# power.net
KiCad netlist of a schematic drawn in Altium Designer
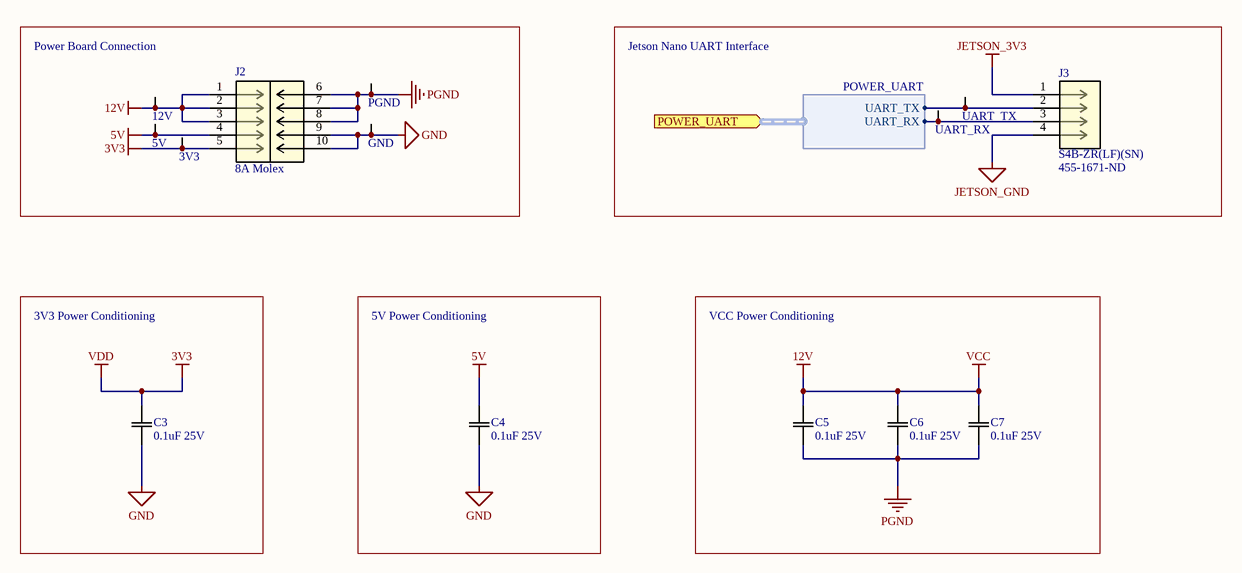
[diagram p0: power.SchDoc]

(export (version "E")
  (design (tool "Eeschema 10.0.6"))
  (components
    (comp (ref "3V3")
      (value "Test Point (Via)")
      (footprint "TP")
      (libsource (lib "AltiumLibraries") (part "Test Point (Via)"))
    )
    (comp (ref "5V")
      (value "Test Point (Via)")
      (footprint "TP")
      (libsource (lib "AltiumLibraries") (part "Test Point (Via)"))
    )
    (comp (ref "12V")
      (value "Test Point (Via)")
      (footprint "TP")
      (libsource (lib "AltiumLibraries") (part "Test Point (Via)"))
    )
    (comp (ref "C3")
      (value "0.1uF 25V")
      (footprint "0805")
      (description "CAP CER 0.1UF 25V X7R 0805/0603")
      (fields (field (name "TOLERANCE") "10%"))
      (libsource (lib "AltiumLibraries") (part "CAP 0.1uF 25V"))
    )
    (comp (ref "C4")
      (value "0.1uF 25V")
      (footprint "0805")
      (description "CAP CER 0.1UF 25V X7R 0805/0603")
      (fields (field (name "TOLERANCE") "10%"))
      (libsource (lib "AltiumLibraries") (part "CAP 0.1uF 25V"))
    )
    (comp (ref "C5")
      (value "0.1uF 25V")
      (footprint "0805")
      (description "CAP CER 0.1UF 25V X7R 0805/0603")
      (fields (field (name "TOLERANCE") "10%"))
      (libsource (lib "AltiumLibraries") (part "CAP 0.1uF 25V"))
    )
    (comp (ref "C6")
      (value "0.1uF 25V")
      (footprint "0805")
      (description "CAP CER 0.1UF 25V X7R 0805/0603")
      (fields (field (name "TOLERANCE") "10%"))
      (libsource (lib "AltiumLibraries") (part "CAP 0.1uF 25V"))
    )
    (comp (ref "C7")
      (value "0.1uF 25V")
      (footprint "0805")
      (description "CAP CER 0.1UF 25V X7R 0805/0603")
      (fields (field (name "TOLERANCE") "10%"))
      (libsource (lib "AltiumLibraries") (part "CAP 0.1uF 25V"))
    )
    (comp (ref "GND")
      (value "Test Point (Via)")
      (footprint "TP")
      (libsource (lib "AltiumLibraries") (part "Test Point (Via)"))
    )
    (comp (ref "J2")
      (value "8A Molex")
      (footprint "MOLEX_0430451012")
      (description "CONN HEADER VERT 10POS 3MM")
      (fields (field (name "MANUFACTURER") "Molex") (field (name "MANUFACTURER PART NUMBER") "0430451012"))
      (libsource (lib "AltiumLibraries") (part "CN HDR 10POS MOLEX 0430451012"))
    )
    (comp (ref "J3")
      (value "S4B-ZR(LF)(SN)")
      (footprint "CN S4B-ZR(LF)(SN)_JST")
      (description "Connector Header Through Hole, Right Angle 4 position 0.059\" (1.50mm)")
      (fields
        (field (name "SUPPLIER PART NUMBER 1") "455-1671-ND")
        (field (name "COPYRIGHT") "Copyright (C) 2021 Ultra Librarian. All rights reserved.")
      )
      (libsource (lib "AltiumLibraries") (part "CN HDR 4POS JST ZR"))
    )
    (comp (ref "PGND")
      (value "Test Point (Via)")
      (footprint "TP")
      (libsource (lib "AltiumLibraries") (part "Test Point (Via)"))
    )
    (comp (ref "UART_RX")
      (value "Test Point (Via)")
      (footprint "TP")
      (libsource (lib "AltiumLibraries") (part "Test Point (Via)"))
    )
    (comp (ref "UART_TX")
      (value "Test Point (Via)")
      (footprint "TP")
      (libsource (lib "AltiumLibraries") (part "Test Point (Via)"))
    )
  )
  (nets
    (net (code "3") (name "3V3") (class "Default")
      (node (ref "3V3") (pin "1") (pinfunction "1_1") (pintype "passive"))
      (node (ref "C3") (pin "1") (pinfunction "C1_1") (pintype "passive"))
      (node (ref "J2") (pin "5") (pinfunction "5_5") (pintype "passive"))
    )
    (net (code "4") (name "5V") (class "Default")
      (node (ref "5V") (pin "1") (pinfunction "1_1") (pintype "passive"))
      (node (ref "C4") (pin "1") (pinfunction "C1_1") (pintype "passive"))
      (node (ref "J2") (pin "4") (pinfunction "4_4") (pintype "passive"))
    )
    (net (code "5") (name "12V") (class "Default")
      (node (ref "12V") (pin "1") (pinfunction "1_1") (pintype "passive"))
      (node (ref "C5") (pin "1") (pinfunction "C1_1") (pintype "passive"))
      (node (ref "C6") (pin "1") (pinfunction "C1_1") (pintype "passive"))
      (node (ref "C7") (pin "1") (pinfunction "C1_1") (pintype "passive"))
      (node (ref "J2") (pin "1") (pinfunction "1_1") (pintype "passive"))
      (node (ref "J2") (pin "2") (pinfunction "2_2") (pintype "passive"))
      (node (ref "J2") (pin "3") (pinfunction "3_3") (pintype "passive"))
    )
    (net (code "6") (name "GND") (class "Default")
      (node (ref "C3") (pin "2") (pinfunction "C2_2") (pintype "passive"))
      (node (ref "C4") (pin "2") (pinfunction "C2_2") (pintype "passive"))
      (node (ref "GND") (pin "1") (pinfunction "1_1") (pintype "passive"))
      (node (ref "J2") (pin "10") (pinfunction "10_10") (pintype "passive"))
      (node (ref "J2") (pin "9") (pinfunction "9_9") (pintype "passive"))
    )
    (net (code "7") (name "JETSON_3V3") (class "Default")
      (node (ref "J3") (pin "1") (pinfunction "1_1") (pintype "passive"))
    )
    (net (code "8") (name "JETSON_GND") (class "Default")
      (node (ref "J3") (pin "4") (pinfunction "4_4") (pintype "passive"))
    )
    (net (code "9") (name "Net-(J3-Pad2)") (class "Default")
      (node (ref "J3") (pin "2") (pinfunction "2_2") (pintype "passive"))
      (node (ref "UART_TX") (pin "1") (pinfunction "1_1") (pintype "passive"))
    )
    (net (code "10") (name "Net-(J3-Pad3)") (class "Default")
      (node (ref "J3") (pin "3") (pinfunction "3_3") (pintype "passive"))
      (node (ref "UART_RX") (pin "1") (pinfunction "1_1") (pintype "passive"))
    )
    (net (code "11") (name "PGND") (class "Default")
      (node (ref "C5") (pin "2") (pinfunction "C2_2") (pintype "passive"))
      (node (ref "C6") (pin "2") (pinfunction "C2_2") (pintype "passive"))
      (node (ref "C7") (pin "2") (pinfunction "C2_2") (pintype "passive"))
      (node (ref "J2") (pin "6") (pinfunction "6_6") (pintype "passive"))
      (node (ref "J2") (pin "7") (pinfunction "7_7") (pintype "passive"))
      (node (ref "J2") (pin "8") (pinfunction "8_8") (pintype "passive"))
      (node (ref "PGND") (pin "1") (pinfunction "1_1") (pintype "passive"))
    )
  )
)
